# Pulser.net
KiCad netlist of a schematic drawn in Altium Designer
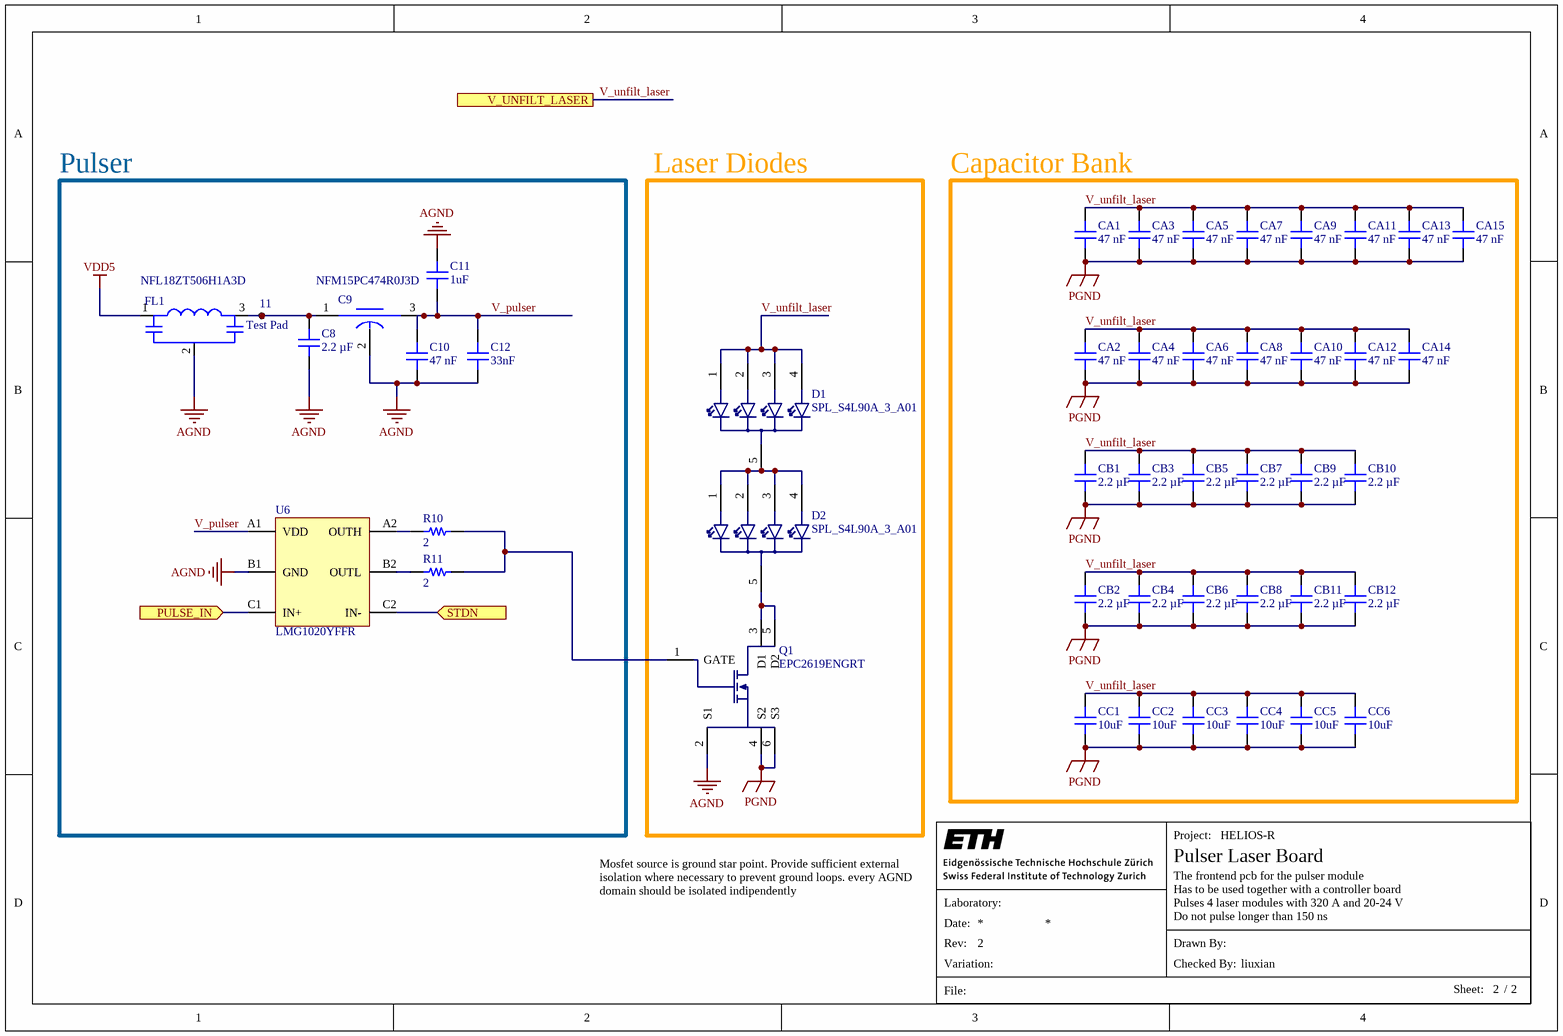
[diagram p0: Pulser.SchDoc]

(export (version "E")
  (design (tool "Eeschema 10.0.6"))
  (components
    (comp (ref "11")
      (value "Test Pad")
      (footprint "Pad-0.6mm")
      (description "0.6mm SMT Test Pad")
      (libsource (lib "ld_pulser") (part "Test Pad"))
    )
    (comp (ref "C8")
      (value "2.2 µF")
      (footprint "CAP 0603_1608")
      (description "CAP CER 2.2UF 50V X5R 0603")
      (fields
        (field (name "PART NUMBER") "GRM188R61H225KE11D")
        (field (name "MANUFACTURER") "Murata Electronics")
      )
      (libsource (lib "ld_pulser") (part "GRM188R61H225KE11D"))
    )
    (comp (ref "C9")
      (value "NFM15PC474R0J3D")
      (footprint "FP-NFM15-0_05-MFG")
      (description "CAP Feed Through, 470 nF, 6.3V, 2A, 3 Pin(s)")
      (fields (field (name "TOLERANCE") "20%") (field (name "MANUFACTURER") "Murata"))
      (libsource (lib "ld_pulser") (part "CMP-06053-000537-1"))
    )
    (comp (ref "C10")
      (value "47 nF")
      (footprint "CAPC0510X35N")
      (description "CAP CER 47 nF, 50V, 20%  X7R  0204")
      (fields
        (field (name "MANUFACTURER_PART_NUMBER") "CGAEA1X7R1H473M030BC")
        (field (name "MOUSER PART NUMBER") "810-CGAEA1X7R1H473M0")
      )
      (libsource (lib "ld_pulser") (part "CGAEA1X7R1H473M030BC"))
    )
    (comp (ref "C11")
      (value "1uF")
      (footprint "FP-LLL152-0_2-MFG")
      (description "CAP LOW L CER 1UF 6.3V X7T 0204")
      (fields
        (field (name "MANUFACTURER") "Murata")
        (field (name "MANUFACTURER PART NUMBER") "LLL152D70J105ME01D")
      )
      (libsource (lib "ld_pulser") (part "CMP-06035-062610-1"))
    )
    (comp (ref "C12")
      (value "33nF")
      (footprint "FP-LLL03T-0_03-IPC_C")
      (description "CAP LOW L CER 33nF 25V X5R 0102")
      (fields
        (field (name "MANUFACTURER") "Murata")
        (field (name "MANUFACTURER PART NUMBER") "LLL03TR61E333KE01L")
      )
      (libsource (lib "ld_pulser") (part "LLL03TR61E333KE01"))
    )
    (comp (ref "CA1")
      (value "47 nF")
      (footprint "CAPC0510X35N")
      (description "CAP CER 47 nF, 50V, 20%  X7R  0204")
      (fields
        (field (name "MANUFACTURER_PART_NUMBER") "CGAEA1X7R1H473M030BC")
        (field (name "MOUSER PART NUMBER") "810-CGAEA1X7R1H473M0")
      )
      (libsource (lib "ld_pulser") (part "CGAEA1X7R1H473M030BC"))
    )
    (comp (ref "CA2")
      (value "47 nF")
      (footprint "CAPC0510X35N")
      (description "CAP CER 47 nF, 50V, 20%  X7R  0204")
      (fields
        (field (name "MANUFACTURER_PART_NUMBER") "CGAEA1X7R1H473M030BC")
        (field (name "MOUSER PART NUMBER") "810-CGAEA1X7R1H473M0")
      )
      (libsource (lib "ld_pulser") (part "CGAEA1X7R1H473M030BC"))
    )
    (comp (ref "CA3")
      (value "47 nF")
      (footprint "CAPC0510X35N")
      (description "CAP CER 47 nF, 50V, 20%  X7R  0204")
      (fields
        (field (name "MANUFACTURER_PART_NUMBER") "CGAEA1X7R1H473M030BC")
        (field (name "MOUSER PART NUMBER") "810-CGAEA1X7R1H473M0")
      )
      (libsource (lib "ld_pulser") (part "CGAEA1X7R1H473M030BC"))
    )
    (comp (ref "CA4")
      (value "47 nF")
      (footprint "CAPC0510X35N")
      (description "CAP CER 47 nF, 50V, 20%  X7R  0204")
      (fields
        (field (name "MANUFACTURER_PART_NUMBER") "CGAEA1X7R1H473M030BC")
        (field (name "MOUSER PART NUMBER") "810-CGAEA1X7R1H473M0")
      )
      (libsource (lib "ld_pulser") (part "CGAEA1X7R1H473M030BC"))
    )
    (comp (ref "CA5")
      (value "47 nF")
      (footprint "CAPC0510X35N")
      (description "CAP CER 47 nF, 50V, 20%  X7R  0204")
      (fields
        (field (name "MANUFACTURER_PART_NUMBER") "CGAEA1X7R1H473M030BC")
        (field (name "MOUSER PART NUMBER") "810-CGAEA1X7R1H473M0")
      )
      (libsource (lib "ld_pulser") (part "CGAEA1X7R1H473M030BC"))
    )
    (comp (ref "CA6")
      (value "47 nF")
      (footprint "CAPC0510X35N")
      (description "CAP CER 47 nF, 50V, 20%  X7R  0204")
      (fields
        (field (name "MANUFACTURER_PART_NUMBER") "CGAEA1X7R1H473M030BC")
        (field (name "MOUSER PART NUMBER") "810-CGAEA1X7R1H473M0")
      )
      (libsource (lib "ld_pulser") (part "CGAEA1X7R1H473M030BC"))
    )
    (comp (ref "CA7")
      (value "47 nF")
      (footprint "CAPC0510X35N")
      (description "CAP CER 47 nF, 50V, 20%  X7R  0204")
      (fields
        (field (name "MANUFACTURER_PART_NUMBER") "CGAEA1X7R1H473M030BC")
        (field (name "MOUSER PART NUMBER") "810-CGAEA1X7R1H473M0")
      )
      (libsource (lib "ld_pulser") (part "CGAEA1X7R1H473M030BC"))
    )
    (comp (ref "CA8")
      (value "47 nF")
      (footprint "CAPC0510X35N")
      (description "CAP CER 47 nF, 50V, 20%  X7R  0204")
      (fields
        (field (name "MANUFACTURER_PART_NUMBER") "CGAEA1X7R1H473M030BC")
        (field (name "MOUSER PART NUMBER") "810-CGAEA1X7R1H473M0")
      )
      (libsource (lib "ld_pulser") (part "CGAEA1X7R1H473M030BC"))
    )
    (comp (ref "CA9")
      (value "47 nF")
      (footprint "CAPC0510X35N")
      (description "CAP CER 47 nF, 50V, 20%  X7R  0204")
      (fields
        (field (name "MANUFACTURER_PART_NUMBER") "CGAEA1X7R1H473M030BC")
        (field (name "MOUSER PART NUMBER") "810-CGAEA1X7R1H473M0")
      )
      (libsource (lib "ld_pulser") (part "CGAEA1X7R1H473M030BC"))
    )
    (comp (ref "CA10")
      (value "47 nF")
      (footprint "CAPC0510X35N")
      (description "CAP CER 47 nF, 50V, 20%  X7R  0204")
      (fields
        (field (name "MANUFACTURER_PART_NUMBER") "CGAEA1X7R1H473M030BC")
        (field (name "MOUSER PART NUMBER") "810-CGAEA1X7R1H473M0")
      )
      (libsource (lib "ld_pulser") (part "CGAEA1X7R1H473M030BC"))
    )
    (comp (ref "CA11")
      (value "47 nF")
      (footprint "CAPC0510X35N")
      (description "CAP CER 47 nF, 50V, 20%  X7R  0204")
      (fields
        (field (name "MANUFACTURER_PART_NUMBER") "CGAEA1X7R1H473M030BC")
        (field (name "MOUSER PART NUMBER") "810-CGAEA1X7R1H473M0")
      )
      (libsource (lib "ld_pulser") (part "CGAEA1X7R1H473M030BC"))
    )
    (comp (ref "CA12")
      (value "47 nF")
      (footprint "CAPC0510X35N")
      (description "CAP CER 47 nF, 50V, 20%  X7R  0204")
      (fields
        (field (name "MANUFACTURER_PART_NUMBER") "CGAEA1X7R1H473M030BC")
        (field (name "MOUSER PART NUMBER") "810-CGAEA1X7R1H473M0")
      )
      (libsource (lib "ld_pulser") (part "CGAEA1X7R1H473M030BC"))
    )
    (comp (ref "CA13")
      (value "47 nF")
      (footprint "CAPC0510X35N")
      (description "CAP CER 47 nF, 50V, 20%  X7R  0204")
      (fields
        (field (name "MANUFACTURER_PART_NUMBER") "CGAEA1X7R1H473M030BC")
        (field (name "MOUSER PART NUMBER") "810-CGAEA1X7R1H473M0")
      )
      (libsource (lib "ld_pulser") (part "CGAEA1X7R1H473M030BC"))
    )
    (comp (ref "CA14")
      (value "47 nF")
      (footprint "CAPC0510X35N")
      (description "CAP CER 47 nF, 50V, 20%  X7R  0204")
      (fields
        (field (name "MANUFACTURER_PART_NUMBER") "CGAEA1X7R1H473M030BC")
        (field (name "MOUSER PART NUMBER") "810-CGAEA1X7R1H473M0")
      )
      (libsource (lib "ld_pulser") (part "CGAEA1X7R1H473M030BC"))
    )
    (comp (ref "CA15")
      (value "47 nF")
      (footprint "CAPC0510X35N")
      (description "CAP CER 47 nF, 50V, 20%  X7R  0204")
      (fields
        (field (name "MANUFACTURER_PART_NUMBER") "CGAEA1X7R1H473M030BC")
        (field (name "MOUSER PART NUMBER") "810-CGAEA1X7R1H473M0")
      )
      (libsource (lib "ld_pulser") (part "CGAEA1X7R1H473M030BC"))
    )
    (comp (ref "CB1")
      (value "2.2 µF")
      (footprint "CAP 0603_1608")
      (description "CAP CER 2.2UF 50V X5R 0603")
      (fields
        (field (name "PART NUMBER") "GRM188R61H225KE11D")
        (field (name "MANUFACTURER") "Murata Electronics")
      )
      (libsource (lib "ld_pulser") (part "GRM188R61H225KE11D"))
    )
    (comp (ref "CB2")
      (value "2.2 µF")
      (footprint "CAP 0603_1608")
      (description "CAP CER 2.2UF 50V X5R 0603")
      (fields
        (field (name "PART NUMBER") "GRM188R61H225KE11D")
        (field (name "MANUFACTURER") "Murata Electronics")
      )
      (libsource (lib "ld_pulser") (part "GRM188R61H225KE11D"))
    )
    (comp (ref "CB3")
      (value "2.2 µF")
      (footprint "CAP 0603_1608")
      (description "CAP CER 2.2UF 50V X5R 0603")
      (fields
        (field (name "PART NUMBER") "GRM188R61H225KE11D")
        (field (name "MANUFACTURER") "Murata Electronics")
      )
      (libsource (lib "ld_pulser") (part "GRM188R61H225KE11D"))
    )
    (comp (ref "CB4")
      (value "2.2 µF")
      (footprint "CAP 0603_1608")
      (description "CAP CER 2.2UF 50V X5R 0603")
      (fields
        (field (name "PART NUMBER") "GRM188R61H225KE11D")
        (field (name "MANUFACTURER") "Murata Electronics")
      )
      (libsource (lib "ld_pulser") (part "GRM188R61H225KE11D"))
    )
    (comp (ref "CB5")
      (value "2.2 µF")
      (footprint "CAP 0603_1608")
      (description "CAP CER 2.2UF 50V X5R 0603")
      (fields
        (field (name "PART NUMBER") "GRM188R61H225KE11D")
        (field (name "MANUFACTURER") "Murata Electronics")
      )
      (libsource (lib "ld_pulser") (part "GRM188R61H225KE11D"))
    )
    (comp (ref "CB6")
      (value "2.2 µF")
      (footprint "CAP 0603_1608")
      (description "CAP CER 2.2UF 50V X5R 0603")
      (fields
        (field (name "PART NUMBER") "GRM188R61H225KE11D")
        (field (name "MANUFACTURER") "Murata Electronics")
      )
      (libsource (lib "ld_pulser") (part "GRM188R61H225KE11D"))
    )
    (comp (ref "CB7")
      (value "2.2 µF")
      (footprint "CAP 0603_1608")
      (description "CAP CER 2.2UF 50V X5R 0603")
      (fields
        (field (name "PART NUMBER") "GRM188R61H225KE11D")
        (field (name "MANUFACTURER") "Murata Electronics")
      )
      (libsource (lib "ld_pulser") (part "GRM188R61H225KE11D"))
    )
    (comp (ref "CB8")
      (value "2.2 µF")
      (footprint "CAP 0603_1608")
      (description "CAP CER 2.2UF 50V X5R 0603")
      (fields
        (field (name "PART NUMBER") "GRM188R61H225KE11D")
        (field (name "MANUFACTURER") "Murata Electronics")
      )
      (libsource (lib "ld_pulser") (part "GRM188R61H225KE11D"))
    )
    (comp (ref "CB9")
      (value "2.2 µF")
      (footprint "CAP 0603_1608")
      (description "CAP CER 2.2UF 50V X5R 0603")
      (fields
        (field (name "PART NUMBER") "GRM188R61H225KE11D")
        (field (name "MANUFACTURER") "Murata Electronics")
      )
      (libsource (lib "ld_pulser") (part "GRM188R61H225KE11D"))
    )
    (comp (ref "CB10")
      (value "2.2 µF")
      (footprint "CAP 0603_1608")
      (description "CAP CER 2.2UF 50V X5R 0603")
      (fields
        (field (name "PART NUMBER") "GRM188R61H225KE11D")
        (field (name "MANUFACTURER") "Murata Electronics")
      )
      (libsource (lib "ld_pulser") (part "GRM188R61H225KE11D"))
    )
    (comp (ref "CB11")
      (value "2.2 µF")
      (footprint "CAP 0603_1608")
      (description "CAP CER 2.2UF 50V X5R 0603")
      (fields
        (field (name "PART NUMBER") "GRM188R61H225KE11D")
        (field (name "MANUFACTURER") "Murata Electronics")
      )
      (libsource (lib "ld_pulser") (part "GRM188R61H225KE11D"))
    )
    (comp (ref "CB12")
      (value "2.2 µF")
      (footprint "CAP 0603_1608")
      (description "CAP CER 2.2UF 50V X5R 0603")
      (fields
        (field (name "PART NUMBER") "GRM188R61H225KE11D")
        (field (name "MANUFACTURER") "Murata Electronics")
      )
      (libsource (lib "ld_pulser") (part "GRM188R61H225KE11D"))
    )
    (comp (ref "CC1")
      (value "10uF")
      (footprint "CAP 0603_1608")
      (description "CAP CER 10UF 25V X5R 0603")
      (fields
        (field (name "MANUFACTURER") "Murata")
        (field (name "MANUFACTURER PART NUMBER") "ZRB18AR61E106ME01L")
      )
      (libsource (lib "ld_pulser") (part "ZRB18AR61E106ME01L"))
    )
    (comp (ref "CC2")
      (value "10uF")
      (footprint "CAP 0603_1608")
      (description "CAP CER 10UF 25V X5R 0603")
      (fields
        (field (name "MANUFACTURER") "Murata")
        (field (name "MANUFACTURER PART NUMBER") "ZRB18AR61E106ME01L")
      )
      (libsource (lib "ld_pulser") (part "ZRB18AR61E106ME01L"))
    )
    (comp (ref "CC3")
      (value "10uF")
      (footprint "CAP 0603_1608")
      (description "CAP CER 10UF 25V X5R 0603")
      (fields
        (field (name "MANUFACTURER") "Murata")
        (field (name "MANUFACTURER PART NUMBER") "ZRB18AR61E106ME01L")
      )
      (libsource (lib "ld_pulser") (part "ZRB18AR61E106ME01L"))
    )
    (comp (ref "CC4")
      (value "10uF")
      (footprint "CAP 0603_1608")
      (description "CAP CER 10UF 25V X5R 0603")
      (fields
        (field (name "MANUFACTURER") "Murata")
        (field (name "MANUFACTURER PART NUMBER") "ZRB18AR61E106ME01L")
      )
      (libsource (lib "ld_pulser") (part "ZRB18AR61E106ME01L"))
    )
    (comp (ref "CC5")
      (value "10uF")
      (footprint "CAP 0603_1608")
      (description "CAP CER 10UF 25V X5R 0603")
      (fields
        (field (name "MANUFACTURER") "Murata")
        (field (name "MANUFACTURER PART NUMBER") "ZRB18AR61E106ME01L")
      )
      (libsource (lib "ld_pulser") (part "ZRB18AR61E106ME01L"))
    )
    (comp (ref "CC6")
      (value "10uF")
      (footprint "CAP 0603_1608")
      (description "CAP CER 10UF 25V X5R 0603")
      (fields
        (field (name "MANUFACTURER") "Murata")
        (field (name "MANUFACTURER PART NUMBER") "ZRB18AR61E106ME01L")
      )
      (libsource (lib "ld_pulser") (part "ZRB18AR61E106ME01L"))
    )
    (comp (ref "D1")
      (value "SPL_S4L90A_3_A01")
      (footprint "SPLS4L90A_3A01")
      (description "Diode Laser")
      (fields
        (field (name "MANUFACTURER_PART_NUMBER") "SPL S4L90A_3 A01")
        (field (name "MOUSER PART NUMBER") "720-SPLS4L90A3A01")
      )
      (libsource (lib "ld_pulser") (part "SPL_S4L90A_3_A01"))
    )
    (comp (ref "D2")
      (value "SPL_S4L90A_3_A01")
      (footprint "SPLS4L90A_3A01")
      (description "Diode Laser")
      (fields
        (field (name "MANUFACTURER_PART_NUMBER") "SPL S4L90A_3 A01")
        (field (name "MOUSER PART NUMBER") "720-SPLS4L90A3A01")
      )
      (libsource (lib "ld_pulser") (part "SPL_S4L90A_3_A01"))
    )
    (comp (ref "FL1")
      (value "NFL18ZT506H1A3D")
      (footprint "NFL18ST107H1A3D")
      (description "LC Filter")
      (fields (field (name "MOUSER PART NUMBER") "81-NFL18ZT506H1A3D"))
      (libsource (lib "ld_pulser") (part "NFL18ZT506H1A3D"))
    )
    (comp (ref "Q1")
      (value "EPC2619ENGRT")
      (footprint "EPC2619ENGRT")
      (description "Transistor eGaN")
      (libsource (lib "ld_pulser") (part "EPC2619ENGRT"))
    )
    (comp (ref "R10")
      (value "2")
      (footprint "RES 0201_0603")
      (description "RES SMD 2 OHM 1% 1/20W 0201")
      (fields
        (field (name "MANUFACTURER") "Panasonic")
        (field (name "MANUFACTURER PART NUMBER") "ERJ-1GNJ2R0C")
      )
      (libsource (lib "ld_pulser") (part "ERJ-1GNJ2R0C"))
    )
    (comp (ref "R11")
      (value "2")
      (footprint "RES 0201_0603")
      (description "RES SMD 2 OHM 1% 1/20W 0201")
      (fields
        (field (name "MANUFACTURER") "Panasonic")
        (field (name "MANUFACTURER PART NUMBER") "ERJ-1GNJ2R0C")
      )
      (libsource (lib "ld_pulser") (part "ERJ-1GNJ2R0C"))
    )
    (comp (ref "U6")
      (value "LMG1020YFFR")
      (footprint "BGA6C40P2X3_86X126X62")
      (description "IC Pulser")
      (fields (field (name "MOUSER PART NUMBER") "595-LMG1020YFFR"))
      (libsource (lib "ld_pulser") (part "LMG1020YFFR"))
    )
  )
  (nets
    (net (code "1") (name "/PULSE_IN") (class "Default")
      (node (ref "U6") (pin "C1") (pinfunction "IN+_C1") (pintype "passive"))
    )
    (net (code "2") (name "/STDN") (class "Default")
      (node (ref "U6") (pin "C2") (pinfunction "IN-_C2") (pintype "passive"))
    )
    (net (code "3") (name "/V_pulser") (class "Default")
      (node (ref "C10") (pin "2") (pinfunction "2_2") (pintype "passive"))
      (node (ref "C11") (pin "1") (pinfunction "1_1") (pintype "passive"))
      (node (ref "C12") (pin "2") (pinfunction "2_2") (pintype "passive"))
      (node (ref "C9") (pin "3") (pinfunction "Output_3") (pintype "passive"))
      (node (ref "U6") (pin "A1") (pinfunction "VDD_A1") (pintype "passive"))
    )
    (net (code "4") (name "/V_unfilt_laser") (class "Default")
      (node (ref "CA1") (pin "2") (pinfunction "2_2") (pintype "passive"))
      (node (ref "CA10") (pin "2") (pinfunction "2_2") (pintype "passive"))
      (node (ref "CA11") (pin "2") (pinfunction "2_2") (pintype "passive"))
      (node (ref "CA12") (pin "1") (pinfunction "1_1") (pintype "passive"))
      (node (ref "CA13") (pin "1") (pinfunction "1_1") (pintype "passive"))
      (node (ref "CA14") (pin "2") (pinfunction "2_2") (pintype "passive"))
      (node (ref "CA15") (pin "2") (pinfunction "2_2") (pintype "passive"))
      (node (ref "CA2") (pin "2") (pinfunction "2_2") (pintype "passive"))
      (node (ref "CA3") (pin "2") (pinfunction "2_2") (pintype "passive"))
      (node (ref "CA4") (pin "2") (pinfunction "2_2") (pintype "passive"))
      (node (ref "CA5") (pin "2") (pinfunction "2_2") (pintype "passive"))
      (node (ref "CA6") (pin "1") (pinfunction "1_1") (pintype "passive"))
      (node (ref "CA7") (pin "2") (pinfunction "2_2") (pintype "passive"))
      (node (ref "CA8") (pin "2") (pinfunction "2_2") (pintype "passive"))
      (node (ref "CA9") (pin "2") (pinfunction "2_2") (pintype "passive"))
      (node (ref "CB1") (pin "2") (pinfunction "2_2") (pintype "passive"))
      (node (ref "CB10") (pin "2") (pinfunction "2_2") (pintype "passive"))
      (node (ref "CB11") (pin "2") (pinfunction "2_2") (pintype "passive"))
      (node (ref "CB12") (pin "2") (pinfunction "2_2") (pintype "passive"))
      (node (ref "CB2") (pin "2") (pinfunction "2_2") (pintype "passive"))
      (node (ref "CB3") (pin "2") (pinfunction "2_2") (pintype "passive"))
      (node (ref "CB4") (pin "2") (pinfunction "2_2") (pintype "passive"))
      (node (ref "CB5") (pin "2") (pinfunction "2_2") (pintype "passive"))
      (node (ref "CB6") (pin "2") (pinfunction "2_2") (pintype "passive"))
      (node (ref "CB7") (pin "2") (pinfunction "2_2") (pintype "passive"))
      (node (ref "CB8") (pin "2") (pinfunction "2_2") (pintype "passive"))
      (node (ref "CB9") (pin "2") (pinfunction "2_2") (pintype "passive"))
      (node (ref "CC1") (pin "2") (pinfunction "2_2") (pintype "passive"))
      (node (ref "CC2") (pin "2") (pinfunction "2_2") (pintype "passive"))
      (node (ref "CC3") (pin "2") (pinfunction "2_2") (pintype "passive"))
      (node (ref "CC4") (pin "2") (pinfunction "2_2") (pintype "passive"))
      (node (ref "CC5") (pin "2") (pinfunction "2_2") (pintype "passive"))
      (node (ref "CC6") (pin "2") (pinfunction "2_2") (pintype "passive"))
      (node (ref "D1") (pin "1") (pinfunction "ANODE_CH1_1") (pintype "passive"))
      (node (ref "D1") (pin "2") (pinfunction "ANODE_CH2_2") (pintype "passive"))
      (node (ref "D1") (pin "3") (pinfunction "ANODE_CH3_3") (pintype "passive"))
      (node (ref "D1") (pin "4") (pinfunction "ANODE_CH4_4") (pintype "passive"))
    )
    (net (code "5") (name "AGND") (class "Default")
      (node (ref "C10") (pin "1") (pinfunction "1_1") (pintype "passive"))
      (node (ref "C11") (pin "2") (pinfunction "2_2") (pintype "passive"))
      (node (ref "C12") (pin "1") (pinfunction "1_1") (pintype "passive"))
      (node (ref "C8") (pin "1") (pinfunction "1_1") (pintype "passive"))
      (node (ref "C9") (pin "2") (pinfunction "GND_2") (pintype "passive"))
      (node (ref "FL1") (pin "2") (pinfunction "2_2") (pintype "passive"))
      (node (ref "Q1") (pin "2") (pinfunction "S1_2") (pintype "passive"))
      (node (ref "U6") (pin "B1") (pinfunction "GND_B1") (pintype "passive"))
    )
    (net (code "6") (name "Net-(C9-Input)") (class "Default")
      (node (ref "11") (pin "1") (pinfunction "1_1") (pintype "passive"))
      (node (ref "C8") (pin "2") (pinfunction "2_2") (pintype "passive"))
      (node (ref "C9") (pin "1") (pinfunction "Input_1") (pintype "passive"))
      (node (ref "FL1") (pin "3") (pinfunction "3_3") (pintype "passive"))
    )
    (net (code "7") (name "Net-(D1-COM_CATHODE)") (class "Default")
      (node (ref "D1") (pin "5") (pinfunction "COM_CATHODE_5") (pintype "passive"))
      (node (ref "D2") (pin "1") (pinfunction "ANODE_CH1_1") (pintype "passive"))
      (node (ref "D2") (pin "2") (pinfunction "ANODE_CH2_2") (pintype "passive"))
      (node (ref "D2") (pin "3") (pinfunction "ANODE_CH3_3") (pintype "passive"))
      (node (ref "D2") (pin "4") (pinfunction "ANODE_CH4_4") (pintype "passive"))
    )
    (net (code "8") (name "Net-(D2-COM_CATHODE)") (class "Default")
      (node (ref "D2") (pin "5") (pinfunction "COM_CATHODE_5") (pintype "passive"))
      (node (ref "Q1") (pin "3") (pinfunction "D1_3") (pintype "passive"))
      (node (ref "Q1") (pin "5") (pinfunction "D2_5") (pintype "passive"))
    )
    (net (code "9") (name "Net-(Q1-GATE)") (class "Default")
      (node (ref "Q1") (pin "1") (pinfunction "GATE_1") (pintype "passive"))
      (node (ref "R10") (pin "2") (pinfunction "2_2") (pintype "passive"))
      (node (ref "R11") (pin "2") (pinfunction "2_2") (pintype "passive"))
    )
    (net (code "10") (name "Net-(U6-OUTH)") (class "Default")
      (node (ref "R10") (pin "1") (pinfunction "1_1") (pintype "passive"))
      (node (ref "U6") (pin "A2") (pinfunction "OUTH_A2") (pintype "passive"))
    )
    (net (code "11") (name "Net-(U6-OUTL)") (class "Default")
      (node (ref "R11") (pin "1") (pinfunction "1_1") (pintype "passive"))
      (node (ref "U6") (pin "B2") (pinfunction "OUTL_B2") (pintype "passive"))
    )
    (net (code "12") (name "PGND") (class "Default")
      (node (ref "CA1") (pin "1") (pinfunction "1_1") (pintype "passive"))
      (node (ref "CA10") (pin "1") (pinfunction "1_1") (pintype "passive"))
      (node (ref "CA11") (pin "1") (pinfunction "1_1") (pintype "passive"))
      (node (ref "CA12") (pin "2") (pinfunction "2_2") (pintype "passive"))
      (node (ref "CA13") (pin "2") (pinfunction "2_2") (pintype "passive"))
      (node (ref "CA14") (pin "1") (pinfunction "1_1") (pintype "passive"))
      (node (ref "CA15") (pin "1") (pinfunction "1_1") (pintype "passive"))
      (node (ref "CA2") (pin "1") (pinfunction "1_1") (pintype "passive"))
      (node (ref "CA3") (pin "1") (pinfunction "1_1") (pintype "passive"))
      (node (ref "CA4") (pin "1") (pinfunction "1_1") (pintype "passive"))
      (node (ref "CA5") (pin "1") (pinfunction "1_1") (pintype "passive"))
      (node (ref "CA6") (pin "2") (pinfunction "2_2") (pintype "passive"))
      (node (ref "CA7") (pin "1") (pinfunction "1_1") (pintype "passive"))
      (node (ref "CA8") (pin "1") (pinfunction "1_1") (pintype "passive"))
      (node (ref "CA9") (pin "1") (pinfunction "1_1") (pintype "passive"))
      (node (ref "CB1") (pin "1") (pinfunction "1_1") (pintype "passive"))
      (node (ref "CB10") (pin "1") (pinfunction "1_1") (pintype "passive"))
      (node (ref "CB11") (pin "1") (pinfunction "1_1") (pintype "passive"))
      (node (ref "CB12") (pin "1") (pinfunction "1_1") (pintype "passive"))
      (node (ref "CB2") (pin "1") (pinfunction "1_1") (pintype "passive"))
      (node (ref "CB3") (pin "1") (pinfunction "1_1") (pintype "passive"))
      (node (ref "CB4") (pin "1") (pinfunction "1_1") (pintype "passive"))
      (node (ref "CB5") (pin "1") (pinfunction "1_1") (pintype "passive"))
      (node (ref "CB6") (pin "1") (pinfunction "1_1") (pintype "passive"))
      (node (ref "CB7") (pin "1") (pinfunction "1_1") (pintype "passive"))
      (node (ref "CB8") (pin "1") (pinfunction "1_1") (pintype "passive"))
      (node (ref "CB9") (pin "1") (pinfunction "1_1") (pintype "passive"))
      (node (ref "CC1") (pin "1") (pinfunction "1_1") (pintype "passive"))
      (node (ref "CC2") (pin "1") (pinfunction "1_1") (pintype "passive"))
      (node (ref "CC3") (pin "1") (pinfunction "1_1") (pintype "passive"))
      (node (ref "CC4") (pin "1") (pinfunction "1_1") (pintype "passive"))
      (node (ref "CC5") (pin "1") (pinfunction "1_1") (pintype "passive"))
      (node (ref "CC6") (pin "1") (pinfunction "1_1") (pintype "passive"))
      (node (ref "Q1") (pin "4") (pinfunction "S2_4") (pintype "passive"))
      (node (ref "Q1") (pin "6") (pinfunction "S3_6") (pintype "passive"))
    )
    (net (code "13") (name "VDD5") (class "Default")
      (node (ref "FL1") (pin "1") (pinfunction "1_1") (pintype "passive"))
    )
  )
)
